# untitled.net
KiCad netlist of a schematic drawn in EAGLE
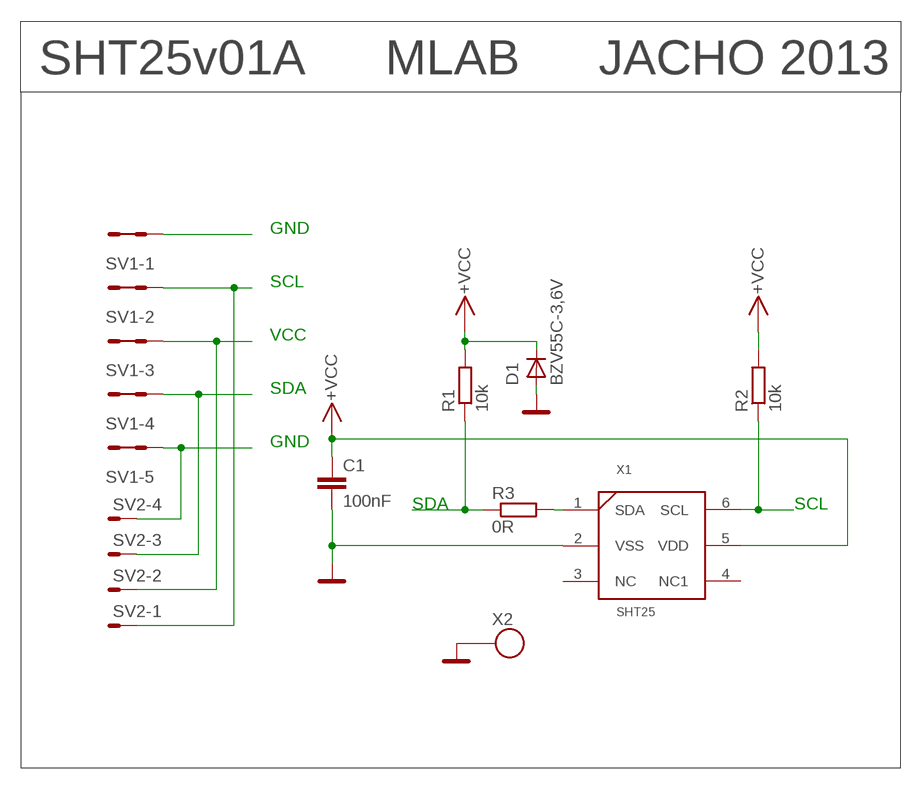
[diagram p0: schematic, sheet 1]

(export (version "E")
  (design (tool "Eeschema 10.0.6"))
  (components
    (comp (ref "C1")
      (value "100nF")
      (footprint "eagle-import:C0805")
      (libsource (lib "eagle-import") (part "C-EUC0805"))
    )
    (comp (ref "D1")
      (value "BZV55C-3,6V")
      (footprint "eagle-import:SMA")
      (libsource (lib "eagle-import") (part "D-OB.SMA"))
    )
    (comp (ref "R1")
      (value "10k")
      (footprint "eagle-import:R0805")
      (libsource (lib "eagle-import") (part "R-EU_R0805"))
    )
    (comp (ref "R2")
      (value "10k")
      (footprint "eagle-import:R0805")
      (libsource (lib "eagle-import") (part "R-EU_R0805"))
    )
    (comp (ref "R3")
      (value "0R")
      (footprint "eagle-import:R0805")
      (libsource (lib "eagle-import") (part "R-EU_R0805"))
    )
    (comp (ref "SV1")
      (value "MA05-2")
      (footprint "eagle-import:MA05-2")
      (libsource (lib "eagle-import") (part "MA05-2"))
    )
    (comp (ref "SV2")
      (value "SMD_MA04-01")
      (footprint "eagle-import:SMD_MA04-1")
      (libsource (lib "eagle-import") (part "SMD_MA04-01"))
    )
    (comp (ref "X1")
      (value "SHT25")
      (footprint "eagle-import:SHT25")
      (libsource (lib "eagle-import") (part "SHT25"))
    )
    (comp (ref "X2")
      (value "SROUB3M")
      (footprint "eagle-import:SROUB3M")
      (libsource (lib "eagle-import") (part "SROUB3M"))
    )
  )
  (nets
    (net (code "1") (name "+VCC") (class "Default")
      (node (ref "C1") (pin "1") (pinfunction "1_1") (pintype "passive"))
      (node (ref "D1") (pin "K") (pinfunction "C_K") (pintype "passive"))
      (node (ref "R1") (pin "2") (pinfunction "2_2") (pintype "passive"))
      (node (ref "R2") (pin "2") (pinfunction "2_2") (pintype "passive"))
      (node (ref "SV1") (pin "5") (pinfunction "K_5") (pintype "passive"))
      (node (ref "SV1") (pin "6") (pinfunction "K_6") (pintype "passive"))
      (node (ref "SV2") (pin "2") (pinfunction "P$1_2") (pintype "passive"))
      (node (ref "X1") (pin "5") (pinfunction "VDD_5") (pintype "bidirectional"))
    )
    (net (code "2") (name "/SCL") (class "Default")
      (node (ref "R2") (pin "1") (pinfunction "1_1") (pintype "passive"))
      (node (ref "SV1") (pin "3") (pinfunction "K_3") (pintype "passive"))
      (node (ref "SV1") (pin "4") (pinfunction "K_4") (pintype "passive"))
      (node (ref "SV2") (pin "1") (pinfunction "P$1_1") (pintype "passive"))
      (node (ref "X1") (pin "6") (pinfunction "SCL_6") (pintype "bidirectional"))
    )
    (net (code "3") (name "/SDA") (class "Default")
      (node (ref "R1") (pin "1") (pinfunction "1_1") (pintype "passive"))
      (node (ref "R3") (pin "1") (pinfunction "1_1") (pintype "passive"))
      (node (ref "SV1") (pin "7") (pinfunction "K_7") (pintype "passive"))
      (node (ref "SV1") (pin "8") (pinfunction "K_8") (pintype "passive"))
      (node (ref "SV2") (pin "3") (pinfunction "P$1_3") (pintype "passive"))
    )
    (net (code "4") (name "GND") (class "Default")
      (node (ref "C1") (pin "2") (pinfunction "2_2") (pintype "passive"))
      (node (ref "D1") (pin "A") (pinfunction "A_A") (pintype "passive"))
      (node (ref "SV1") (pin "1") (pinfunction "K_1") (pintype "passive"))
      (node (ref "SV1") (pin "10") (pinfunction "K_10") (pintype "passive"))
      (node (ref "SV1") (pin "2") (pinfunction "K_2") (pintype "passive"))
      (node (ref "SV1") (pin "9") (pinfunction "K_9") (pintype "passive"))
      (node (ref "SV2") (pin "4") (pinfunction "P$1_4") (pintype "passive"))
      (node (ref "X1") (pin "2") (pinfunction "VSS_2") (pintype "bidirectional"))
      (node (ref "X2") (pin "P$1") (pinfunction "P$1_P$1") (pintype "bidirectional"))
    )
    (net (code "5") (name "Net-(X1-SDA)") (class "Default")
      (node (ref "R3") (pin "2") (pinfunction "2_2") (pintype "passive"))
      (node (ref "X1") (pin "1") (pinfunction "SDA_1") (pintype "bidirectional"))
    )
    (net (code "6") (name "unconnected-(X1-NC-Pad3)") (class "Default")
      (node (ref "X1") (pin "3") (pinfunction "NC_3") (pintype "bidirectional"))
    )
    (net (code "7") (name "unconnected-(X1-NC1-Pad4)") (class "Default")
      (node (ref "X1") (pin "4") (pinfunction "NC1_4") (pintype "bidirectional"))
    )
  )
)
